# SCH_Alexey_Beekeeper_2023-01-21.net
KiCad netlist of a schematic drawn in EasyEDA
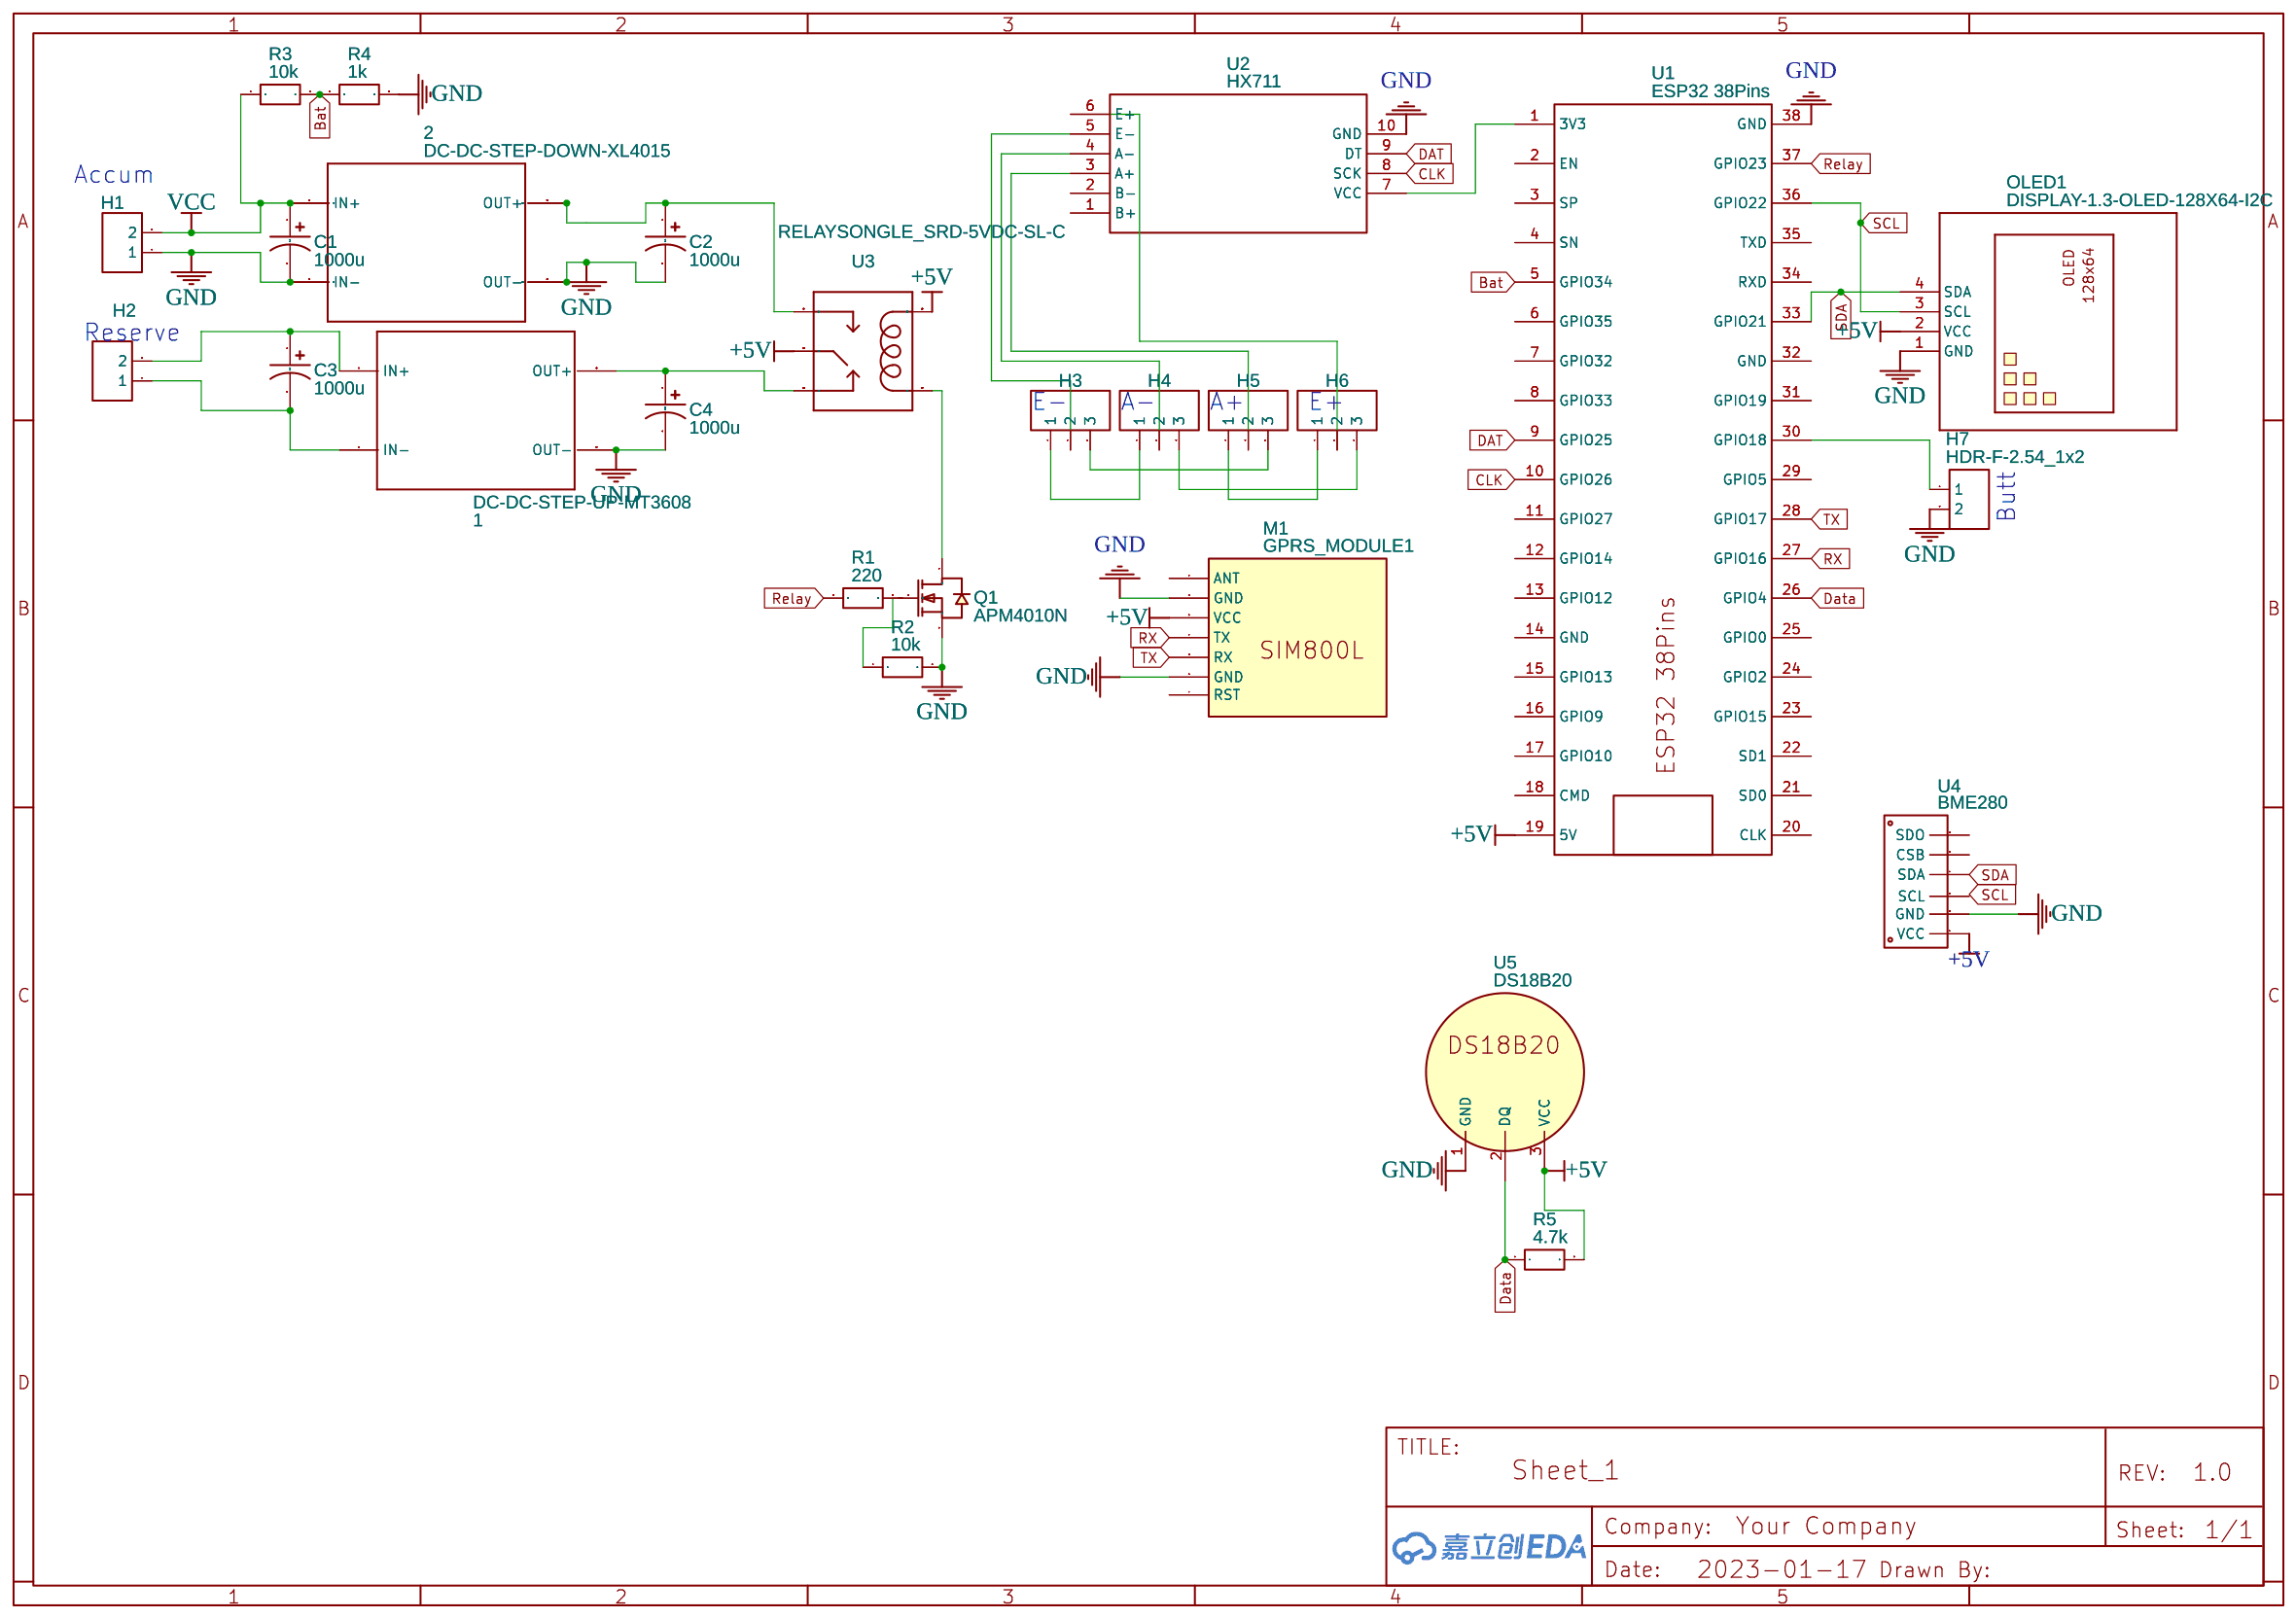
[diagram p0: schematic sheet]

(export (version "E")
  (design (tool "Eeschema 10.0.6"))
  (components
    (comp (ref "1") (value "DC-DC-STEP-UP-MT3608") (libsource (lib "") (part "DC-DC-STEP-UP-MT3608")))
    (comp (ref "2") (value "DC-DC-STEP-DOWN-XL4015") (libsource (lib "") (part "DC-DC-STEP-DOWN-XL4015")))
    (comp (ref "C1") (value "1000u") (libsource (lib "") (part "CE_TH_D12.5×F5.0_US_1")))
    (comp (ref "C2") (value "1000u") (libsource (lib "") (part "CE_TH_D12.5×F5.0_US")))
    (comp (ref "C3") (value "1000u") (libsource (lib "") (part "CE_TH_D12.5×F5.0_US_1")))
    (comp (ref "C4") (value "1000u") (libsource (lib "") (part "CE_TH_D12.5×F5.0_US")))
    (comp (ref "H1")
      (value "HDR-F-2.54_1x2")
      (fields (field (name "BOM_Supplier Part") "C49661"))
      (libsource (lib "") (part "HDR-F-2.54_1x2"))
    )
    (comp (ref "H2")
      (value "HDR-F-2.54_1x2")
      (fields (field (name "BOM_Supplier Part") "C49661"))
      (libsource (lib "") (part "HDR-F-2.54_1x2"))
    )
    (comp (ref "H3")
      (value "HDR-F-2.54_1x3")
      (fields (field (name "BOM_Supplier Part") "C146690"))
      (libsource (lib "") (part "HDR-F-2.54_1x3"))
    )
    (comp (ref "H4")
      (value "HDR-F-2.54_1x3")
      (fields (field (name "BOM_Supplier Part") "C146690"))
      (libsource (lib "") (part "HDR-F-2.54_1x3"))
    )
    (comp (ref "H5")
      (value "HDR-F-2.54_1x3")
      (fields (field (name "BOM_Supplier Part") "C146690"))
      (libsource (lib "") (part "HDR-F-2.54_1x3"))
    )
    (comp (ref "H6")
      (value "HDR-F-2.54_1x3")
      (fields (field (name "BOM_Supplier Part") "C146690"))
      (libsource (lib "") (part "HDR-F-2.54_1x3"))
    )
    (comp (ref "H7")
      (value "HDR-F-2.54_1x2")
      (fields (field (name "BOM_Supplier Part") "C49661"))
      (libsource (lib "") (part "HDR-F-2.54_1x2_1"))
    )
    (comp (ref "M1")
      (value "GPRS_MODULE1")
      (fields
        (field (name "BOM_Manufacturer Part") "SIM800L")
        (field (name "BOM_Supplier Part") "SIM800L EVB")
      )
      (libsource (lib "") (part "GPRS_MODULE1"))
    )
    (comp (ref "OLED1")
      (value "DISPLAY-1.3-OLED-128X64-I2C")
      (libsource (lib "") (part "DISPLAY-1.3-OLED-128X64-I2C"))
    )
    (comp (ref "Q1")
      (value "APM4010N")
      (fields
        (field (name "BOM_Manufacturer Part") "APM4010NUC")
        (field (name "BOM_Supplier Part") "C724986")
      )
      (libsource (lib "") (part "APM4010N"))
    )
    (comp (ref "R1") (value "220") (libsource (lib "") (part "R_0603_EU")))
    (comp (ref "R2") (value "10k") (libsource (lib "") (part "R_1206_EU")))
    (comp (ref "R3") (value "10k") (libsource (lib "") (part "R_1206_EU")))
    (comp (ref "R4") (value "1k") (libsource (lib "") (part "R_1206_EU")))
    (comp (ref "R5") (value "4.7k") (libsource (lib "") (part "R_1206_EU")))
    (comp (ref "U1") (value "ESP32 38Pins") (libsource (lib "") (part "ESP32 38Pins")))
    (comp (ref "U2") (value "HX711") (libsource (lib "") (part "HX711")))
    (comp (ref "U3")
      (value "RELAYSONGLE_SRD-5VDC-SL-C")
      (libsource (lib "") (part "RELAYSONGLE_SRD-5VDC-SL-C"))
    )
    (comp (ref "U4") (value "BME280") (libsource (lib "") (part "BME280")))
    (comp (ref "U5") (value "DS18B20") (libsource (lib "") (part "DS18B20")))
  )
  (nets
    (net (code "1") (name "+5V") (class "Default")
      (node (ref "M1") (pin "3") (pinfunction "VCC_3") (pintype "input"))
      (node (ref "OLED1") (pin "2") (pinfunction "VCC_2") (pintype "bidirectional"))
      (node (ref "R5") (pin "2") (pinfunction "2_2") (pintype "unspecified"))
      (node (ref "U1") (pin "19") (pinfunction "5V_19") (pintype "unspecified"))
      (node (ref "U3") (pin "COIL2") (pinfunction "COIL2_COIL2") (pintype "unspecified"))
      (node (ref "U3") (pin "COMMON") (pinfunction "MAIN_COMMON") (pintype "unspecified"))
      (node (ref "U4") (pin "1") (pinfunction "VCC_1") (pintype "unspecified"))
      (node (ref "U5") (pin "3") (pinfunction "VCC_3") (pintype "input"))
    )
    (net (code "2") (name "Bat") (class "Default")
      (node (ref "R3") (pin "2") (pinfunction "2_2") (pintype "unspecified"))
      (node (ref "R4") (pin "1") (pinfunction "1_1") (pintype "unspecified"))
      (node (ref "U1") (pin "5") (pinfunction "GPIO34_5") (pintype "unspecified"))
    )
    (net (code "3") (name "CLK") (class "Default")
      (node (ref "U1") (pin "10") (pinfunction "GPIO26_10") (pintype "unspecified"))
      (node (ref "U2") (pin "8") (pinfunction "SCK_8") (pintype "unspecified"))
    )
    (net (code "4") (name "DAT") (class "Default")
      (node (ref "U1") (pin "9") (pinfunction "GPIO25_9") (pintype "unspecified"))
      (node (ref "U2") (pin "9") (pinfunction "DT_9") (pintype "unspecified"))
    )
    (net (code "5") (name "Data") (class "Default")
      (node (ref "R5") (pin "1") (pinfunction "1_1") (pintype "unspecified"))
      (node (ref "U1") (pin "26") (pinfunction "GPIO4_26") (pintype "unspecified"))
      (node (ref "U5") (pin "2") (pinfunction "DQ_2") (pintype "unspecified"))
    )
    (net (code "6") (name "GND") (class "Default")
      (node (ref "1") (pin "OUT-") (pinfunction "OUT-_OUT-") (pintype "bidirectional"))
      (node (ref "2") (pin "I-") (pinfunction "IN-_I-") (pintype "bidirectional"))
      (node (ref "2") (pin "IN-") (pinfunction "IN-_IN-") (pintype "bidirectional"))
      (node (ref "2") (pin "O-") (pinfunction "OUT-_O-") (pintype "bidirectional"))
      (node (ref "2") (pin "OUT-") (pinfunction "OUT-_OUT-") (pintype "bidirectional"))
      (node (ref "C1") (pin "2") (pinfunction "2_2") (pintype "unspecified"))
      (node (ref "C2") (pin "2") (pinfunction "2_2") (pintype "unspecified"))
      (node (ref "C4") (pin "2") (pinfunction "2_2") (pintype "unspecified"))
      (node (ref "H1") (pin "1") (pinfunction "1_1") (pintype "input"))
      (node (ref "H7") (pin "2") (pinfunction "2_2") (pintype "input"))
      (node (ref "M1") (pin "2") (pinfunction "GND_2") (pintype "input"))
      (node (ref "M1") (pin "6") (pinfunction "GND_6") (pintype "input"))
      (node (ref "OLED1") (pin "1") (pinfunction "GND_1") (pintype "bidirectional"))
      (node (ref "Q1") (pin "3") (pinfunction "S_3") (pintype "unspecified"))
      (node (ref "R2") (pin "2") (pinfunction "2_2") (pintype "unspecified"))
      (node (ref "R4") (pin "2") (pinfunction "2_2") (pintype "unspecified"))
      (node (ref "U1") (pin "38") (pinfunction "GND_38") (pintype "unspecified"))
      (node (ref "U2") (pin "10") (pinfunction "GND_10") (pintype "unspecified"))
      (node (ref "U4") (pin "2") (pinfunction "GND_2") (pintype "unspecified"))
      (node (ref "U5") (pin "1") (pinfunction "GND_1") (pintype "output"))
    )
    (net (code "7") (name "Net-(1-PadIN+)") (class "Default")
      (node (ref "1") (pin "IN+") (pinfunction "IN+_IN+") (pintype "bidirectional"))
      (node (ref "C3") (pin "1") (pinfunction "1_1") (pintype "unspecified"))
      (node (ref "H2") (pin "2") (pinfunction "2_2") (pintype "input"))
    )
    (net (code "8") (name "Net-(1-PadIN-)") (class "Default")
      (node (ref "1") (pin "IN-") (pinfunction "IN-_IN-") (pintype "bidirectional"))
      (node (ref "C3") (pin "2") (pinfunction "2_2") (pintype "unspecified"))
      (node (ref "H2") (pin "1") (pinfunction "1_1") (pintype "input"))
    )
    (net (code "9") (name "Net-(H3-Pad1)") (class "Default")
      (node (ref "H3") (pin "1") (pinfunction "1_1") (pintype "input"))
      (node (ref "H4") (pin "1") (pinfunction "1_1") (pintype "input"))
    )
    (net (code "10") (name "Net-(H3-Pad3)") (class "Default")
      (node (ref "H3") (pin "3") (pinfunction "3_3") (pintype "input"))
      (node (ref "H5") (pin "3") (pinfunction "3_3") (pintype "input"))
    )
    (net (code "11") (name "Net-(H4-Pad3)") (class "Default")
      (node (ref "H4") (pin "3") (pinfunction "3_3") (pintype "input"))
      (node (ref "H6") (pin "3") (pinfunction "3_3") (pintype "input"))
    )
    (net (code "12") (name "Net-(H5-Pad1)") (class "Default")
      (node (ref "H5") (pin "1") (pinfunction "1_1") (pintype "input"))
      (node (ref "H6") (pin "1") (pinfunction "1_1") (pintype "input"))
    )
    (net (code "13") (name "Net-(Q1-D)") (class "Default")
      (node (ref "Q1") (pin "2") (pinfunction "D_2") (pintype "unspecified"))
      (node (ref "U3") (pin "COIL1") (pinfunction "COIL1_COIL1") (pintype "unspecified"))
    )
    (net (code "14") (name "Net-(Q1-G)") (class "Default")
      (node (ref "Q1") (pin "1") (pinfunction "G_1") (pintype "unspecified"))
      (node (ref "R2") (pin "1") (pinfunction "1_1") (pintype "unspecified"))
    )
    (net (code "15") (name "Net-(U1-3V3)") (class "Default")
      (node (ref "U1") (pin "1") (pinfunction "3V3_1") (pintype "unspecified"))
      (node (ref "U2") (pin "7") (pinfunction "VCC_7") (pintype "unspecified"))
    )
    (net (code "16") (name "Net-(U1-GPIO18)") (class "Default")
      (node (ref "H7") (pin "1") (pinfunction "1_1") (pintype "input"))
      (node (ref "U1") (pin "30") (pinfunction "GPIO18_30") (pintype "unspecified"))
    )
    (net (code "17") (name "Net-(U2-A+)") (class "Default")
      (node (ref "H5") (pin "2") (pinfunction "2_2") (pintype "input"))
      (node (ref "U2") (pin "3") (pinfunction "A+_3") (pintype "unspecified"))
    )
    (net (code "18") (name "Net-(U2-A-)") (class "Default")
      (node (ref "H4") (pin "2") (pinfunction "2_2") (pintype "input"))
      (node (ref "U2") (pin "4") (pinfunction "A-_4") (pintype "unspecified"))
    )
    (net (code "19") (name "Net-(U2-E+)") (class "Default")
      (node (ref "H6") (pin "2") (pinfunction "2_2") (pintype "input"))
      (node (ref "U2") (pin "6") (pinfunction "E+_6") (pintype "unspecified"))
    )
    (net (code "20") (name "Net-(U2-E-)") (class "Default")
      (node (ref "H3") (pin "2") (pinfunction "2_2") (pintype "input"))
      (node (ref "U2") (pin "5") (pinfunction "E-_5") (pintype "unspecified"))
    )
    (net (code "21") (name "Net-(U3-NC)") (class "Default")
      (node (ref "1") (pin "OUT+") (pinfunction "OUT+_OUT+") (pintype "bidirectional"))
      (node (ref "C4") (pin "1") (pinfunction "1_1") (pintype "unspecified"))
      (node (ref "U3") (pin "CLOSED") (pinfunction "NC_CLOSED") (pintype "unspecified"))
    )
    (net (code "22") (name "Net-(U3-NO)") (class "Default")
      (node (ref "2") (pin "O+") (pinfunction "OUT+_O+") (pintype "bidirectional"))
      (node (ref "2") (pin "OUT+") (pinfunction "OUT+_OUT+") (pintype "bidirectional"))
      (node (ref "C2") (pin "1") (pinfunction "1_1") (pintype "unspecified"))
      (node (ref "U3") (pin "OPEN") (pinfunction "NO_OPEN") (pintype "unspecified"))
    )
    (net (code "23") (name "RX") (class "Default")
      (node (ref "M1") (pin "4") (pinfunction "TX_4") (pintype "input"))
      (node (ref "U1") (pin "27") (pinfunction "GPIO16_27") (pintype "unspecified"))
    )
    (net (code "24") (name "Relay") (class "Default")
      (node (ref "R1") (pin "1") (pinfunction "1_1") (pintype "unspecified"))
      (node (ref "U1") (pin "37") (pinfunction "GPIO23_37") (pintype "unspecified"))
    )
    (net (code "25") (name "SCL") (class "Default")
      (node (ref "OLED1") (pin "3") (pinfunction "SCL_3") (pintype "bidirectional"))
      (node (ref "U1") (pin "36") (pinfunction "GPIO22_36") (pintype "unspecified"))
    )
    (net (code "26") (name "SDA") (class "Default")
      (node (ref "OLED1") (pin "4") (pinfunction "SDA_4") (pintype "bidirectional"))
      (node (ref "U1") (pin "33") (pinfunction "GPIO21_33") (pintype "unspecified"))
      (node (ref "U4") (pin "4") (pinfunction "SDA_4") (pintype "unspecified"))
    )
    (net (code "27") (name "TX") (class "Default")
      (node (ref "M1") (pin "5") (pinfunction "RX_5") (pintype "input"))
      (node (ref "U1") (pin "28") (pinfunction "GPIO17_28") (pintype "unspecified"))
    )
    (net (code "28") (name "VCC") (class "Default")
      (node (ref "2") (pin "I+") (pinfunction "IN+_I+") (pintype "bidirectional"))
      (node (ref "2") (pin "IN+") (pinfunction "IN+_IN+") (pintype "bidirectional"))
      (node (ref "C1") (pin "1") (pinfunction "1_1") (pintype "unspecified"))
      (node (ref "H1") (pin "2") (pinfunction "2_2") (pintype "input"))
      (node (ref "R3") (pin "1") (pinfunction "1_1") (pintype "unspecified"))
    )
    (net (code "29") (name "unconnected-(M1-ANT-Pad1)") (class "Default")
      (node (ref "M1") (pin "1") (pinfunction "ANT_1") (pintype "input"))
    )
    (net (code "30") (name "unconnected-(M1-RST-Pad7)") (class "Default")
      (node (ref "M1") (pin "7") (pinfunction "RST_7") (pintype "input"))
    )
    (net (code "31") (name "unconnected-(R1-Pad2)") (class "Default")
      (node (ref "R1") (pin "2") (pinfunction "2_2") (pintype "unspecified"))
    )
    (net (code "32") (name "unconnected-(U1-CLK-Pad20)") (class "Default")
      (node (ref "U1") (pin "20") (pinfunction "CLK_20") (pintype "unspecified"))
    )
    (net (code "33") (name "unconnected-(U1-CMD-Pad18)") (class "Default")
      (node (ref "U1") (pin "18") (pinfunction "CMD_18") (pintype "unspecified"))
    )
    (net (code "34") (name "unconnected-(U1-EN-Pad2)") (class "Default")
      (node (ref "U1") (pin "2") (pinfunction "EN_2") (pintype "unspecified"))
    )
    (net (code "35") (name "unconnected-(U1-GND-Pad14)") (class "Default")
      (node (ref "U1") (pin "14") (pinfunction "GND_14") (pintype "unspecified"))
    )
    (net (code "36") (name "unconnected-(U1-GND-Pad32)") (class "Default")
      (node (ref "U1") (pin "32") (pinfunction "GND_32") (pintype "unspecified"))
    )
    (net (code "37") (name "unconnected-(U1-GPIO0-Pad25)") (class "Default")
      (node (ref "U1") (pin "25") (pinfunction "GPIO0_25") (pintype "unspecified"))
    )
    (net (code "38") (name "unconnected-(U1-GPIO2-Pad24)") (class "Default")
      (node (ref "U1") (pin "24") (pinfunction "GPIO2_24") (pintype "unspecified"))
    )
    (net (code "39") (name "unconnected-(U1-GPIO5-Pad29)") (class "Default")
      (node (ref "U1") (pin "29") (pinfunction "GPIO5_29") (pintype "unspecified"))
    )
    (net (code "40") (name "unconnected-(U1-GPIO9-Pad16)") (class "Default")
      (node (ref "U1") (pin "16") (pinfunction "GPIO9_16") (pintype "unspecified"))
    )
    (net (code "41") (name "unconnected-(U1-GPIO10-Pad17)") (class "Default")
      (node (ref "U1") (pin "17") (pinfunction "GPIO10_17") (pintype "unspecified"))
    )
    (net (code "42") (name "unconnected-(U1-GPIO12-Pad13)") (class "Default")
      (node (ref "U1") (pin "13") (pinfunction "GPIO12_13") (pintype "unspecified"))
    )
    (net (code "43") (name "unconnected-(U1-GPIO13-Pad15)") (class "Default")
      (node (ref "U1") (pin "15") (pinfunction "GPIO13_15") (pintype "unspecified"))
    )
    (net (code "44") (name "unconnected-(U1-GPIO14-Pad12)") (class "Default")
      (node (ref "U1") (pin "12") (pinfunction "GPIO14_12") (pintype "unspecified"))
    )
    (net (code "45") (name "unconnected-(U1-GPIO15-Pad23)") (class "Default")
      (node (ref "U1") (pin "23") (pinfunction "GPIO15_23") (pintype "unspecified"))
    )
    (net (code "46") (name "unconnected-(U1-GPIO19-Pad31)") (class "Default")
      (node (ref "U1") (pin "31") (pinfunction "GPIO19_31") (pintype "unspecified"))
    )
    (net (code "47") (name "unconnected-(U1-GPIO27-Pad11)") (class "Default")
      (node (ref "U1") (pin "11") (pinfunction "GPIO27_11") (pintype "unspecified"))
    )
    (net (code "48") (name "unconnected-(U1-GPIO32-Pad7)") (class "Default")
      (node (ref "U1") (pin "7") (pinfunction "GPIO32_7") (pintype "unspecified"))
    )
    (net (code "49") (name "unconnected-(U1-GPIO33-Pad8)") (class "Default")
      (node (ref "U1") (pin "8") (pinfunction "GPIO33_8") (pintype "unspecified"))
    )
    (net (code "50") (name "unconnected-(U1-GPIO35-Pad6)") (class "Default")
      (node (ref "U1") (pin "6") (pinfunction "GPIO35_6") (pintype "unspecified"))
    )
    (net (code "51") (name "unconnected-(U1-RXD-Pad34)") (class "Default")
      (node (ref "U1") (pin "34") (pinfunction "RXD_34") (pintype "unspecified"))
    )
    (net (code "52") (name "unconnected-(U1-SD0-Pad21)") (class "Default")
      (node (ref "U1") (pin "21") (pinfunction "SD0_21") (pintype "unspecified"))
    )
    (net (code "53") (name "unconnected-(U1-SD1-Pad22)") (class "Default")
      (node (ref "U1") (pin "22") (pinfunction "SD1_22") (pintype "unspecified"))
    )
    (net (code "54") (name "unconnected-(U1-SN-Pad4)") (class "Default")
      (node (ref "U1") (pin "4") (pinfunction "SN_4") (pintype "unspecified"))
    )
    (net (code "55") (name "unconnected-(U1-SP-Pad3)") (class "Default")
      (node (ref "U1") (pin "3") (pinfunction "SP_3") (pintype "unspecified"))
    )
    (net (code "56") (name "unconnected-(U1-TXD-Pad35)") (class "Default")
      (node (ref "U1") (pin "35") (pinfunction "TXD_35") (pintype "unspecified"))
    )
    (net (code "57") (name "unconnected-(U2-B+-Pad1)") (class "Default")
      (node (ref "U2") (pin "1") (pinfunction "B+_1") (pintype "unspecified"))
    )
    (net (code "58") (name "unconnected-(U2-B--Pad2)") (class "Default")
      (node (ref "U2") (pin "2") (pinfunction "B-_2") (pintype "unspecified"))
    )
    (net (code "59") (name "unconnected-(U4-CSB-Pad5)") (class "Default")
      (node (ref "U4") (pin "5") (pinfunction "CSB_5") (pintype "unspecified"))
    )
    (net (code "60") (name "unconnected-(U4-SCL-Pad3)") (class "Default")
      (node (ref "U4") (pin "3") (pinfunction "SCL_3") (pintype "unspecified"))
    )
    (net (code "61") (name "unconnected-(U4-SDO-Pad6)") (class "Default")
      (node (ref "U4") (pin "6") (pinfunction "SDO_6") (pintype "unspecified"))
    )
  )
)
